# picB4currentreading.net
KiCad netlist of a schematic drawn in EAGLE
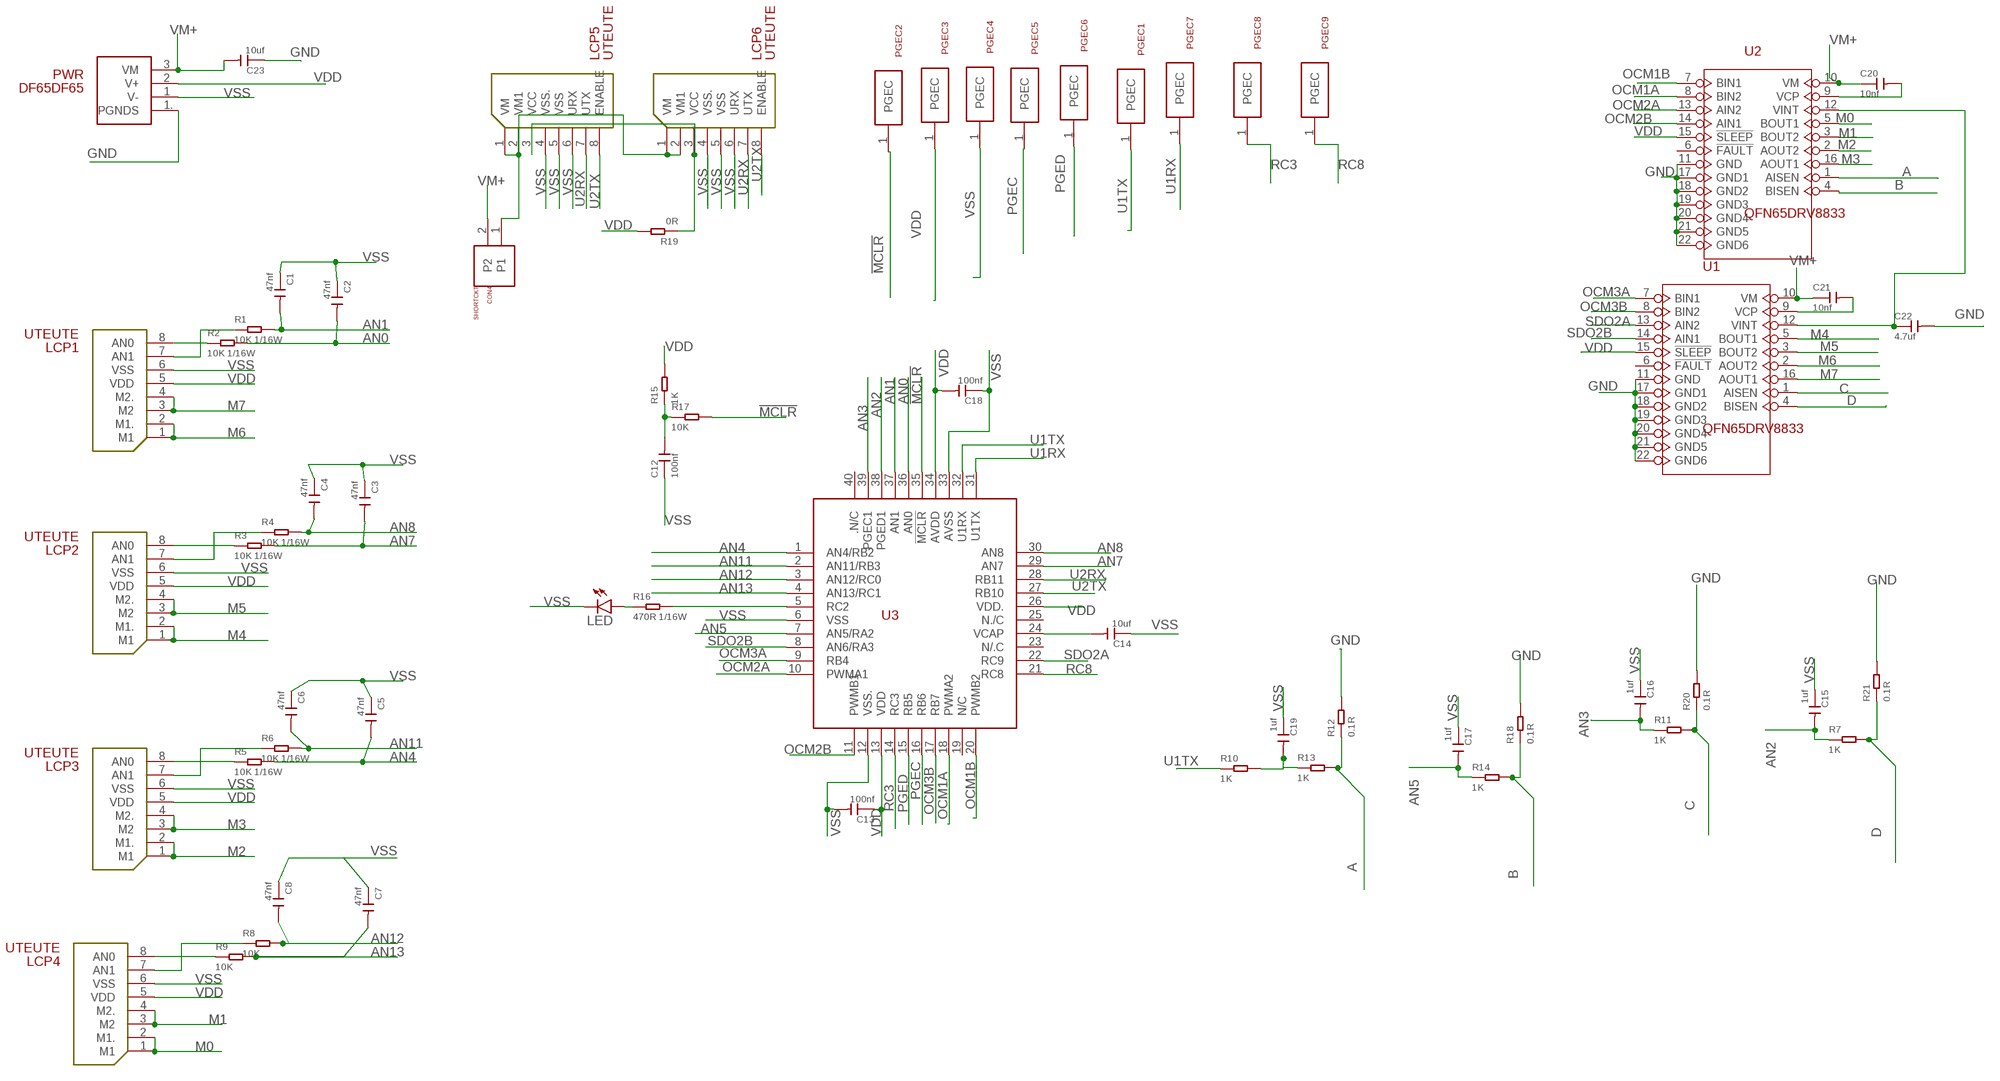
[diagram p0: schematic, sheet 1]

(export (version "E")
  (design (tool "Eeschema 10.0.6"))
  (components
    (comp (ref "C1")
      (value "47nf")
      (footprint "eagle-import:C0402")
      (fields (field (name "MPN") "CC0402KRX7R8BB473"))
      (libsource (lib "eagle-import") (part "CERAMIC-47NF-25V-10%-X7R(0402)"))
    )
    (comp (ref "C2")
      (value "47nf")
      (footprint "eagle-import:C0402")
      (fields (field (name "MPN") "CC0402KRX7R8BB473"))
      (libsource (lib "eagle-import") (part "CERAMIC-47NF-25V-10%-X7R(0402)"))
    )
    (comp (ref "C3")
      (value "47nf")
      (footprint "eagle-import:C0402")
      (fields (field (name "MPN") "CC0402KRX7R8BB473"))
      (libsource (lib "eagle-import") (part "CERAMIC-47NF-25V-10%-X7R(0402)"))
    )
    (comp (ref "C4")
      (value "47nf")
      (footprint "eagle-import:C0402")
      (fields (field (name "MPN") "CC0402KRX7R8BB473"))
      (libsource (lib "eagle-import") (part "CERAMIC-47NF-25V-10%-X7R(0402)"))
    )
    (comp (ref "C5")
      (value "47nf")
      (footprint "eagle-import:C0402")
      (fields (field (name "MPN") "CC0402KRX7R8BB473"))
      (libsource (lib "eagle-import") (part "CERAMIC-47NF-25V-10%-X7R(0402)"))
    )
    (comp (ref "C6")
      (value "47nf")
      (footprint "eagle-import:C0402")
      (fields (field (name "MPN") "CC0402KRX7R8BB473"))
      (libsource (lib "eagle-import") (part "CERAMIC-47NF-25V-10%-X7R(0402)"))
    )
    (comp (ref "C7")
      (value "47nf")
      (footprint "eagle-import:C0402")
      (fields (field (name "MPN") "CC0402KRX7R8BB473"))
      (libsource (lib "eagle-import") (part "CERAMIC-47NF-25V-10%-X7R(0402)"))
    )
    (comp (ref "C8")
      (value "47nf")
      (footprint "eagle-import:C0402")
      (fields (field (name "MPN") "CC0402KRX7R8BB473"))
      (libsource (lib "eagle-import") (part "CERAMIC-47NF-25V-10%-X7R(0402)"))
    )
    (comp (ref "C12")
      (value "100nf")
      (footprint "eagle-import:C0402")
      (fields (field (name "MPN") "CC0402KRX7R8BB104"))
      (libsource (lib "eagle-import") (part "CERAMIC-100NF-25V-10%-X7R(0402)"))
    )
    (comp (ref "C13")
      (value "100nf")
      (footprint "eagle-import:C0402")
      (fields (field (name "MPN") "CC0402KRX7R8BB104"))
      (libsource (lib "eagle-import") (part "CERAMIC-100NF-25V-10%-X7R(0402)"))
    )
    (comp (ref "C14")
      (value "10uf")
      (footprint "eagle-import:C0402")
      (fields (field (name "MPN") "CC0402MRX5R5BB106"))
      (libsource (lib "eagle-import") (part "CERAMIC-10UF-6.3V-20%-X5R(0402)"))
    )
    (comp (ref "C15")
      (value "1uf")
      (footprint "eagle-import:C0402")
      (fields (field (name "MPN") "CC0402KRX5R6BB105"))
      (libsource (lib "eagle-import") (part "CERAMIC-1UF-10V-10%-X5R(0402)"))
    )
    (comp (ref "C16")
      (value "1uf")
      (footprint "eagle-import:C0402")
      (fields (field (name "MPN") "CC0402KRX5R6BB105"))
      (libsource (lib "eagle-import") (part "CERAMIC-1UF-10V-10%-X5R(0402)"))
    )
    (comp (ref "C17")
      (value "1uf")
      (footprint "eagle-import:C0402")
      (fields (field (name "MPN") "CC0402KRX5R6BB105"))
      (libsource (lib "eagle-import") (part "CERAMIC-1UF-10V-10%-X5R(0402)"))
    )
    (comp (ref "C18")
      (value "100nf")
      (footprint "eagle-import:C0402")
      (fields (field (name "MPN") "CC0402KRX7R8BB104"))
      (libsource (lib "eagle-import") (part "CERAMIC-100NF-25V-10%-X7R(0402)"))
    )
    (comp (ref "C19")
      (value "1uf")
      (footprint "eagle-import:C0402")
      (fields (field (name "MPN") "CC0402KRX5R6BB105"))
      (libsource (lib "eagle-import") (part "CERAMIC-1UF-10V-10%-X5R(0402)"))
    )
    (comp (ref "C20")
      (value "10nf")
      (footprint "eagle-import:C0402")
      (fields (field (name "MPN") "CC0402KRX7R9BB103"))
      (libsource (lib "eagle-import") (part "CERAMIC-10NF-50V-10%-X7R(0402)"))
    )
    (comp (ref "C21")
      (value "10nf")
      (footprint "eagle-import:C0402")
      (fields (field (name "MPN") "CC0402KRX7R9BB103"))
      (libsource (lib "eagle-import") (part "CERAMIC-10NF-50V-10%-X7R(0402)"))
    )
    (comp (ref "C22")
      (value "4.7uf")
      (footprint "eagle-import:C0402")
      (fields (field (name "MPN") "CC0402MRX5R5BB475"))
      (libsource (lib "eagle-import") (part "CERAMIC-4.7UF-6.3V-20%-X5R(0402)"))
    )
    (comp (ref "C23")
      (value "10uf")
      (footprint "eagle-import:C0402")
      (fields (field (name "MPN") "CC0402MRX5R5BB106"))
      (libsource (lib "eagle-import") (part "CERAMIC-10UF-6.3V-20%-X5R(0402)"))
    )
    (comp (ref "CON4")
      (value "SHORTCKT")
      (footprint "eagle-import:SHORT")
      (libsource (lib "eagle-import") (part "SHORTCKT"))
    )
    (comp (ref "LCP1")
      (value "UTEUTE")
      (footprint "eagle-import:UTE")
      (libsource (lib "eagle-import") (part "UTEUTE"))
    )
    (comp (ref "LCP2")
      (value "UTEUTE")
      (footprint "eagle-import:UTE")
      (libsource (lib "eagle-import") (part "UTEUTE"))
    )
    (comp (ref "LCP3")
      (value "UTEUTE")
      (footprint "eagle-import:UTE")
      (libsource (lib "eagle-import") (part "UTEUTE"))
    )
    (comp (ref "LCP4")
      (value "UTEUTE")
      (footprint "eagle-import:UTE")
      (libsource (lib "eagle-import") (part "UTEUTE"))
    )
    (comp (ref "LCP5")
      (value "UTEUTE")
      (footprint "eagle-import:UTE")
      (libsource (lib "eagle-import") (part "ute5526(uart)_UTEUTE"))
    )
    (comp (ref "LCP6")
      (value "UTEUTE")
      (footprint "eagle-import:UTE")
      (libsource (lib "eagle-import") (part "ute5526(uart)_UTEUTE"))
    )
    (comp (ref "LED")
      (value "LEDCHIP-LED0603")
      (footprint "eagle-import:CHIP-LED0603")
      (libsource (lib "eagle-import") (part "LEDCHIP-LED0603"))
    )
    (comp (ref "PGEC1")
      (value "PGECPGEC")
      (footprint "eagle-import:PGEC")
      (libsource (lib "eagle-import") (part "PGECPGEC"))
    )
    (comp (ref "PGEC2")
      (value "PGECPGEC")
      (footprint "eagle-import:PGEC")
      (libsource (lib "eagle-import") (part "PGECPGEC"))
    )
    (comp (ref "PGEC3")
      (value "PGECPGEC")
      (footprint "eagle-import:PGEC")
      (libsource (lib "eagle-import") (part "PGECPGEC"))
    )
    (comp (ref "PGEC4")
      (value "PGECPGEC")
      (footprint "eagle-import:PGEC")
      (libsource (lib "eagle-import") (part "PGECPGEC"))
    )
    (comp (ref "PGEC5")
      (value "PGECPGEC")
      (footprint "eagle-import:PGEC")
      (libsource (lib "eagle-import") (part "PGECPGEC"))
    )
    (comp (ref "PGEC6")
      (value "PGECPGEC")
      (footprint "eagle-import:PGEC")
      (libsource (lib "eagle-import") (part "PGECPGEC"))
    )
    (comp (ref "PGEC7")
      (value "PGECPGEC")
      (footprint "eagle-import:PGEC")
      (libsource (lib "eagle-import") (part "PGECPGEC"))
    )
    (comp (ref "PGEC8")
      (value "PGECPGEC")
      (footprint "eagle-import:PGEC")
      (libsource (lib "eagle-import") (part "PGECPGEC"))
    )
    (comp (ref "PGEC9")
      (value "PGECPGEC")
      (footprint "eagle-import:PGEC")
      (libsource (lib "eagle-import") (part "PGECPGEC"))
    )
    (comp (ref "PWR")
      (value "DF65DF65")
      (footprint "eagle-import:DF65")
      (libsource (lib "eagle-import") (part "DF65DF65"))
    )
    (comp (ref "R1")
      (value "10K 1/16W")
      (footprint "eagle-import:R0402")
      (fields (field (name "MPN") "RC0402FR-0710KL"))
      (libsource (lib "eagle-import") (part "SMD-RES-10K-1%-1/16W(0402)"))
    )
    (comp (ref "R2")
      (value "10K 1/16W")
      (footprint "eagle-import:R0402")
      (fields (field (name "MPN") "RC0402FR-0710KL"))
      (libsource (lib "eagle-import") (part "SMD-RES-10K-1%-1/16W(0402)"))
    )
    (comp (ref "R3")
      (value "10K 1/16W")
      (footprint "eagle-import:R0402")
      (fields (field (name "MPN") "RC0402FR-0710KL"))
      (libsource (lib "eagle-import") (part "SMD-RES-10K-1%-1/16W(0402)"))
    )
    (comp (ref "R4")
      (value "10K 1/16W")
      (footprint "eagle-import:R0402")
      (fields (field (name "MPN") "RC0402FR-0710KL"))
      (libsource (lib "eagle-import") (part "SMD-RES-10K-1%-1/16W(0402)"))
    )
    (comp (ref "R5")
      (value "10K 1/16W")
      (footprint "eagle-import:R0402")
      (fields (field (name "MPN") "RC0402FR-0710KL"))
      (libsource (lib "eagle-import") (part "SMD-RES-10K-1%-1/16W(0402)"))
    )
    (comp (ref "R6")
      (value "10K 1/16W")
      (footprint "eagle-import:R0402")
      (fields (field (name "MPN") "RC0402FR-0710KL"))
      (libsource (lib "eagle-import") (part "SMD-RES-10K-1%-1/16W(0402)"))
    )
    (comp (ref "R7")
      (value "1K")
      (footprint "eagle-import:R0402")
      (fields (field (name "MPN") "RC0402JR-071KL"))
      (libsource (lib "eagle-import") (part "SMD-RES-1K-5%-1/16W(0402)"))
    )
    (comp (ref "R8")
      (value "10K")
      (footprint "eagle-import:R0402")
      (fields (field (name "MPN") "RC0402JR-0710KL"))
      (libsource (lib "eagle-import") (part "SMD-RES-10K-5%-1/(0402)"))
    )
    (comp (ref "R9")
      (value "10K")
      (footprint "eagle-import:R0402")
      (fields (field (name "MPN") "RC0402JR-0710KL"))
      (libsource (lib "eagle-import") (part "SMD-RES-10K-5%-1/(0402)"))
    )
    (comp (ref "R10")
      (value "1K")
      (footprint "eagle-import:R0402")
      (fields (field (name "MPN") "RC0402JR-071KL"))
      (libsource (lib "eagle-import") (part "SMD-RES-1K-5%-1/16W(0402)"))
    )
    (comp (ref "R11")
      (value "1K")
      (footprint "eagle-import:R0402")
      (fields (field (name "MPN") "RC0402JR-071KL"))
      (libsource (lib "eagle-import") (part "SMD-RES-1K-5%-1/16W(0402)"))
    )
    (comp (ref "R12")
      (value "0.1R")
      (footprint "eagle-import:R0805")
      (fields (field (name "MPN") "RL0805JR-070R1L"))
      (libsource (lib "eagle-import") (part "SMD-RES-0.1R-5%-1/8W(0805)"))
    )
    (comp (ref "R13")
      (value "1K")
      (footprint "eagle-import:R0402")
      (fields (field (name "MPN") "RC0402JR-071KL"))
      (libsource (lib "eagle-import") (part "SMD-RES-1K-5%-1/16W(0402)"))
    )
    (comp (ref "R14")
      (value "1K")
      (footprint "eagle-import:R0402")
      (fields (field (name "MPN") "RC0402JR-071KL"))
      (libsource (lib "eagle-import") (part "SMD-RES-1K-5%-1/16W(0402)"))
    )
    (comp (ref "R15")
      (value "1K")
      (footprint "eagle-import:R0402")
      (fields (field (name "MPN") "RC0402JR-071KL"))
      (libsource (lib "eagle-import") (part "SMD-RES-1K-5%-1/16W(0402)"))
    )
    (comp (ref "R16")
      (value "470R 1/16W")
      (footprint "eagle-import:R0402")
      (fields (field (name "MPN") "RC0402JR-07470RL"))
      (libsource (lib "eagle-import") (part "SMD-RES-470R-5%-1/16W(0402)"))
    )
    (comp (ref "R17")
      (value "10K")
      (footprint "eagle-import:R0402")
      (fields (field (name "MPN") "RC0402JR-0710KL"))
      (libsource (lib "eagle-import") (part "SMD-RES-10K-5%-1/(0402)"))
    )
    (comp (ref "R18")
      (value "0.1R")
      (footprint "eagle-import:R0805")
      (fields (field (name "MPN") "RL0805JR-070R1L"))
      (libsource (lib "eagle-import") (part "SMD-RES-0.1R-5%-1/8W(0805)"))
    )
    (comp (ref "R19")
      (value "0R")
      (footprint "eagle-import:R0402")
      (fields (field (name "MPN") "RC0402JR-070RL"))
      (libsource (lib "eagle-import") (part "SMD-RES-0R-5%-1/16W(0402)"))
    )
    (comp (ref "R20")
      (value "0.1R")
      (footprint "eagle-import:R0805")
      (fields (field (name "MPN") "RL0805JR-070R1L"))
      (libsource (lib "eagle-import") (part "SMD-RES-0.1R-5%-1/8W(0805)"))
    )
    (comp (ref "R21")
      (value "0.1R")
      (footprint "eagle-import:R0805")
      (fields (field (name "MPN") "RL0805JR-070R1L"))
      (libsource (lib "eagle-import") (part "SMD-RES-0.1R-5%-1/8W(0805)"))
    )
    (comp (ref "U1")
      (value "QFN65DRV8833")
      (footprint "eagle-import:QFN65P400X400X80-17N")
      (libsource (lib "eagle-import") (part "QFN65DRV8833"))
    )
    (comp (ref "U2")
      (value "QFN65DRV8833")
      (footprint "eagle-import:QFN65P400X400X80-17N")
      (libsource (lib "eagle-import") (part "QFN65DRV8833"))
    )
    (comp (ref "U3")
      (value "PIC32MM0064GPL036PIC32MM0064GPL36")
      (footprint "eagle-import:UQFN40MV5X5MM")
      (libsource (lib "eagle-import") (part "PIC32MM0064GPL036PIC32MM0064GPL36"))
    )
  )
  (nets
    (net (code "1") (name "/A") (class "Default")
      (node (ref "R12") (pin "1") (pinfunction "1_1") (pintype "passive"))
      (node (ref "R13") (pin "2") (pinfunction "2_2") (pintype "passive"))
      (node (ref "U2") (pin "1") (pinfunction "AISEN_1") (pintype "bidirectional"))
    )
    (net (code "2") (name "/AN0") (class "Default")
      (node (ref "C2") (pin "2") (pinfunction "2_2") (pintype "passive"))
      (node (ref "R2") (pin "2") (pinfunction "2_2") (pintype "passive"))
      (node (ref "U3") (pin "36") (pinfunction "AN0_36") (pintype "bidirectional"))
    )
    (net (code "3") (name "/AN1") (class "Default")
      (node (ref "C1") (pin "2") (pinfunction "2_2") (pintype "passive"))
      (node (ref "R1") (pin "2") (pinfunction "2_2") (pintype "passive"))
      (node (ref "U3") (pin "37") (pinfunction "AN1_37") (pintype "bidirectional"))
    )
    (net (code "4") (name "/AN2") (class "Default")
      (node (ref "C15") (pin "2") (pinfunction "2_2") (pintype "passive"))
      (node (ref "R7") (pin "1") (pinfunction "1_1") (pintype "passive"))
      (node (ref "U3") (pin "38") (pinfunction "PGED1_38") (pintype "bidirectional"))
    )
    (net (code "5") (name "/AN3") (class "Default")
      (node (ref "C16") (pin "2") (pinfunction "2_2") (pintype "passive"))
      (node (ref "R11") (pin "1") (pinfunction "1_1") (pintype "passive"))
      (node (ref "U3") (pin "39") (pinfunction "PGEC1_39") (pintype "bidirectional"))
    )
    (net (code "6") (name "/AN4") (class "Default")
      (node (ref "C5") (pin "2") (pinfunction "2_2") (pintype "passive"))
      (node (ref "R5") (pin "2") (pinfunction "2_2") (pintype "passive"))
      (node (ref "U3") (pin "1") (pinfunction "AN4/RB2_1") (pintype "bidirectional"))
    )
    (net (code "7") (name "/AN5") (class "Default")
      (node (ref "C17") (pin "2") (pinfunction "2_2") (pintype "passive"))
      (node (ref "R14") (pin "1") (pinfunction "1_1") (pintype "passive"))
      (node (ref "U3") (pin "7") (pinfunction "AN5/RA2_7") (pintype "bidirectional"))
    )
    (net (code "8") (name "/AN7") (class "Default")
      (node (ref "C3") (pin "2") (pinfunction "2_2") (pintype "passive"))
      (node (ref "R3") (pin "2") (pinfunction "2_2") (pintype "passive"))
      (node (ref "U3") (pin "29") (pinfunction "AN7_29") (pintype "bidirectional"))
    )
    (net (code "9") (name "/AN8") (class "Default")
      (node (ref "C4") (pin "2") (pinfunction "2_2") (pintype "passive"))
      (node (ref "R4") (pin "2") (pinfunction "2_2") (pintype "passive"))
      (node (ref "U3") (pin "30") (pinfunction "AN8_30") (pintype "bidirectional"))
    )
    (net (code "10") (name "/AN11") (class "Default")
      (node (ref "C6") (pin "2") (pinfunction "2_2") (pintype "passive"))
      (node (ref "R6") (pin "2") (pinfunction "2_2") (pintype "passive"))
      (node (ref "U3") (pin "2") (pinfunction "AN11/RB3_2") (pintype "bidirectional"))
    )
    (net (code "11") (name "/AN12") (class "Default")
      (node (ref "C8") (pin "2") (pinfunction "2_2") (pintype "passive"))
      (node (ref "R8") (pin "2") (pinfunction "2_2") (pintype "passive"))
      (node (ref "U3") (pin "3") (pinfunction "AN12/RC0_3") (pintype "bidirectional"))
    )
    (net (code "12") (name "/AN13") (class "Default")
      (node (ref "C7") (pin "2") (pinfunction "2_2") (pintype "passive"))
      (node (ref "R9") (pin "2") (pinfunction "2_2") (pintype "passive"))
      (node (ref "U3") (pin "4") (pinfunction "AN13/RC1_4") (pintype "bidirectional"))
    )
    (net (code "13") (name "/B") (class "Default")
      (node (ref "R14") (pin "2") (pinfunction "2_2") (pintype "passive"))
      (node (ref "R18") (pin "1") (pinfunction "1_1") (pintype "passive"))
      (node (ref "U2") (pin "4") (pinfunction "BISEN_4") (pintype "bidirectional"))
    )
    (net (code "14") (name "/C") (class "Default")
      (node (ref "R11") (pin "2") (pinfunction "2_2") (pintype "passive"))
      (node (ref "R20") (pin "1") (pinfunction "1_1") (pintype "passive"))
      (node (ref "U1") (pin "1") (pinfunction "AISEN_1") (pintype "bidirectional"))
    )
    (net (code "15") (name "/D") (class "Default")
      (node (ref "R21") (pin "1") (pinfunction "1_1") (pintype "passive"))
      (node (ref "R7") (pin "2") (pinfunction "2_2") (pintype "passive"))
      (node (ref "U1") (pin "4") (pinfunction "BISEN_4") (pintype "bidirectional"))
    )
    (net (code "16") (name "/GND") (class "Default")
      (node (ref "C22") (pin "2") (pinfunction "2_2") (pintype "passive"))
      (node (ref "C23") (pin "1") (pinfunction "1_1") (pintype "passive"))
      (node (ref "PWR") (pin "1.") (pinfunction "PGNDS_1.") (pintype "bidirectional"))
      (node (ref "R12") (pin "2") (pinfunction "2_2") (pintype "passive"))
      (node (ref "R18") (pin "2") (pinfunction "2_2") (pintype "passive"))
      (node (ref "R20") (pin "2") (pinfunction "2_2") (pintype "passive"))
      (node (ref "R21") (pin "2") (pinfunction "2_2") (pintype "passive"))
      (node (ref "U1") (pin "11") (pinfunction "GND_11") (pintype "bidirectional"))
      (node (ref "U1") (pin "17") (pinfunction "GND1_17") (pintype "bidirectional"))
      (node (ref "U1") (pin "18") (pinfunction "GND2_18") (pintype "bidirectional"))
      (node (ref "U1") (pin "19") (pinfunction "GND3_19") (pintype "bidirectional"))
      (node (ref "U1") (pin "20") (pinfunction "GND4_20") (pintype "bidirectional"))
      (node (ref "U1") (pin "21") (pinfunction "GND5_21") (pintype "bidirectional"))
      (node (ref "U1") (pin "22") (pinfunction "GND6_22") (pintype "bidirectional"))
      (node (ref "U2") (pin "11") (pinfunction "GND_11") (pintype "bidirectional"))
      (node (ref "U2") (pin "17") (pinfunction "GND1_17") (pintype "bidirectional"))
      (node (ref "U2") (pin "18") (pinfunction "GND2_18") (pintype "bidirectional"))
      (node (ref "U2") (pin "19") (pinfunction "GND3_19") (pintype "bidirectional"))
      (node (ref "U2") (pin "20") (pinfunction "GND4_20") (pintype "bidirectional"))
      (node (ref "U2") (pin "21") (pinfunction "GND5_21") (pintype "bidirectional"))
      (node (ref "U2") (pin "22") (pinfunction "GND6_22") (pintype "bidirectional"))
    )
    (net (code "17") (name "/M0") (class "Default")
      (node (ref "LCP4") (pin "1") (pinfunction "M1_1") (pintype "bidirectional"))
      (node (ref "LCP4") (pin "2") (pinfunction "M1._2") (pintype "bidirectional"))
      (node (ref "U2") (pin "5") (pinfunction "BOUT1_5") (pintype "bidirectional"))
    )
    (net (code "18") (name "/M1") (class "Default")
      (node (ref "LCP4") (pin "3") (pinfunction "M2_3") (pintype "bidirectional"))
      (node (ref "LCP4") (pin "4") (pinfunction "M2._4") (pintype "bidirectional"))
      (node (ref "U2") (pin "3") (pinfunction "BOUT2_3") (pintype "bidirectional"))
    )
    (net (code "19") (name "/M2") (class "Default")
      (node (ref "LCP3") (pin "1") (pinfunction "M1_1") (pintype "bidirectional"))
      (node (ref "LCP3") (pin "2") (pinfunction "M1._2") (pintype "bidirectional"))
      (node (ref "U2") (pin "2") (pinfunction "AOUT2_2") (pintype "bidirectional"))
    )
    (net (code "20") (name "/M3") (class "Default")
      (node (ref "LCP3") (pin "3") (pinfunction "M2_3") (pintype "bidirectional"))
      (node (ref "LCP3") (pin "4") (pinfunction "M2._4") (pintype "bidirectional"))
      (node (ref "U2") (pin "16") (pinfunction "AOUT1_16") (pintype "bidirectional"))
    )
    (net (code "21") (name "/M4") (class "Default")
      (node (ref "LCP2") (pin "1") (pinfunction "M1_1") (pintype "bidirectional"))
      (node (ref "LCP2") (pin "2") (pinfunction "M1._2") (pintype "bidirectional"))
      (node (ref "U1") (pin "5") (pinfunction "BOUT1_5") (pintype "bidirectional"))
    )
    (net (code "22") (name "/M5") (class "Default")
      (node (ref "LCP2") (pin "3") (pinfunction "M2_3") (pintype "bidirectional"))
      (node (ref "LCP2") (pin "4") (pinfunction "M2._4") (pintype "bidirectional"))
      (node (ref "U1") (pin "3") (pinfunction "BOUT2_3") (pintype "bidirectional"))
    )
    (net (code "23") (name "/M6") (class "Default")
      (node (ref "LCP1") (pin "1") (pinfunction "M1_1") (pintype "bidirectional"))
      (node (ref "LCP1") (pin "2") (pinfunction "M1._2") (pintype "bidirectional"))
      (node (ref "U1") (pin "2") (pinfunction "AOUT2_2") (pintype "bidirectional"))
    )
    (net (code "24") (name "/M7") (class "Default")
      (node (ref "LCP1") (pin "3") (pinfunction "M2_3") (pintype "bidirectional"))
      (node (ref "LCP1") (pin "4") (pinfunction "M2._4") (pintype "bidirectional"))
      (node (ref "U1") (pin "16") (pinfunction "AOUT1_16") (pintype "bidirectional"))
    )
    (net (code "25") (name "/OCM1A") (class "Default")
      (node (ref "U2") (pin "8") (pinfunction "BIN2_8") (pintype "bidirectional"))
      (node (ref "U3") (pin "18") (pinfunction "PWMA2_18") (pintype "bidirectional"))
    )
    (net (code "26") (name "/OCM1B") (class "Default")
      (node (ref "U2") (pin "7") (pinfunction "BIN1_7") (pintype "bidirectional"))
      (node (ref "U3") (pin "20") (pinfunction "PWMB2_20") (pintype "bidirectional"))
    )
    (net (code "27") (name "/OCM2A") (class "Default")
      (node (ref "U2") (pin "13") (pinfunction "AIN2_13") (pintype "bidirectional"))
      (node (ref "U3") (pin "10") (pinfunction "PWMA1_10") (pintype "bidirectional"))
    )
    (net (code "28") (name "/OCM2B") (class "Default")
      (node (ref "U2") (pin "14") (pinfunction "AIN1_14") (pintype "bidirectional"))
      (node (ref "U3") (pin "11") (pinfunction "PWMB1_11") (pintype "bidirectional"))
    )
    (net (code "29") (name "/OCM3A") (class "Default")
      (node (ref "U1") (pin "7") (pinfunction "BIN1_7") (pintype "bidirectional"))
      (node (ref "U3") (pin "9") (pinfunction "RB4_9") (pintype "bidirectional"))
    )
    (net (code "30") (name "/OCM3B") (class "Default")
      (node (ref "U1") (pin "8") (pinfunction "BIN2_8") (pintype "bidirectional"))
      (node (ref "U3") (pin "17") (pinfunction "RB7_17") (pintype "bidirectional"))
    )
    (net (code "31") (name "/PGEC") (class "Default")
      (node (ref "PGEC5") (pin "1") (pinfunction "PGEC_1") (pintype "bidirectional"))
      (node (ref "U3") (pin "16") (pinfunction "RB6_16") (pintype "bidirectional"))
    )
    (net (code "32") (name "/PGED") (class "Default")
      (node (ref "PGEC6") (pin "1") (pinfunction "PGEC_1") (pintype "bidirectional"))
      (node (ref "U3") (pin "15") (pinfunction "RB5_15") (pintype "bidirectional"))
    )
    (net (code "33") (name "/RC3") (class "Default")
      (node (ref "PGEC8") (pin "1") (pinfunction "PGEC_1") (pintype "bidirectional"))
      (node (ref "U3") (pin "14") (pinfunction "RC3_14") (pintype "bidirectional"))
    )
    (net (code "34") (name "/RC8") (class "Default")
      (node (ref "PGEC9") (pin "1") (pinfunction "PGEC_1") (pintype "bidirectional"))
      (node (ref "U3") (pin "21") (pinfunction "RC8_21") (pintype "bidirectional"))
    )
    (net (code "35") (name "/SDO2A") (class "Default")
      (node (ref "U1") (pin "13") (pinfunction "AIN2_13") (pintype "bidirectional"))
      (node (ref "U3") (pin "22") (pinfunction "RC9_22") (pintype "bidirectional"))
    )
    (net (code "36") (name "/SDO2B") (class "Default")
      (node (ref "U1") (pin "14") (pinfunction "AIN1_14") (pintype "bidirectional"))
      (node (ref "U3") (pin "8") (pinfunction "AN6/RA3_8") (pintype "bidirectional"))
    )
    (net (code "37") (name "/U1RX") (class "Default")
      (node (ref "PGEC7") (pin "1") (pinfunction "PGEC_1") (pintype "bidirectional"))
      (node (ref "U3") (pin "31") (pinfunction "U1TX_31") (pintype "bidirectional"))
    )
    (net (code "38") (name "/U1TX") (class "Default")
      (node (ref "PGEC1") (pin "1") (pinfunction "PGEC_1") (pintype "bidirectional"))
      (node (ref "R10") (pin "1") (pinfunction "1_1") (pintype "passive"))
      (node (ref "U3") (pin "32") (pinfunction "U1RX_32") (pintype "bidirectional"))
    )
    (net (code "39") (name "/U2RX") (class "Default")
      (node (ref "LCP5") (pin "7") (pinfunction "UTX_7") (pintype "bidirectional"))
      (node (ref "LCP6") (pin "7") (pinfunction "UTX_7") (pintype "bidirectional"))
      (node (ref "U3") (pin "28") (pinfunction "RB11_28") (pintype "bidirectional"))
    )
    (net (code "40") (name "/U2TX") (class "Default")
      (node (ref "LCP5") (pin "8") (pinfunction "ENABLE_8") (pintype "bidirectional"))
      (node (ref "LCP6") (pin "8") (pinfunction "ENABLE_8") (pintype "bidirectional"))
      (node (ref "U3") (pin "27") (pinfunction "RB10_27") (pintype "bidirectional"))
    )
    (net (code "41") (name "/VDD") (class "Default")
      (node (ref "C13") (pin "1") (pinfunction "1_1") (pintype "passive"))
      (node (ref "C18") (pin "2") (pinfunction "2_2") (pintype "passive"))
      (node (ref "LCP1") (pin "5") (pinfunction "VDD_5") (pintype "bidirectional"))
      (node (ref "LCP2") (pin "5") (pinfunction "VDD_5") (pintype "bidirectional"))
      (node (ref "LCP3") (pin "5") (pinfunction "VDD_5") (pintype "bidirectional"))
      (node (ref "LCP4") (pin "5") (pinfunction "VDD_5") (pintype "bidirectional"))
      (node (ref "PGEC3") (pin "1") (pinfunction "PGEC_1") (pintype "bidirectional"))
      (node (ref "PWR") (pin "2") (pinfunction "V+_2") (pintype "bidirectional"))
      (node (ref "R15") (pin "2") (pinfunction "2_2") (pintype "passive"))
      (node (ref "R19") (pin "2") (pinfunction "2_2") (pintype "passive"))
      (node (ref "U1") (pin "15") (pinfunction "~{SLEEP}_15") (pintype "bidirectional"))
      (node (ref "U2") (pin "15") (pinfunction "~{SLEEP}_15") (pintype "bidirectional"))
      (node (ref "U3") (pin "13") (pinfunction "VDD_13") (pintype "bidirectional"))
      (node (ref "U3") (pin "26") (pinfunction "VDD._26") (pintype "bidirectional"))
      (node (ref "U3") (pin "34") (pinfunction "AVDD_34") (pintype "bidirectional"))
    )
    (net (code "42") (name "/VM+") (class "Default")
      (node (ref "C20") (pin "1") (pinfunction "1_1") (pintype "passive"))
      (node (ref "C21") (pin "1") (pinfunction "1_1") (pintype "passive"))
      (node (ref "C23") (pin "2") (pinfunction "2_2") (pintype "passive"))
      (node (ref "CON4") (pin "2") (pinfunction "P2_2") (pintype "bidirectional"))
      (node (ref "PWR") (pin "3") (pinfunction "VM_3") (pintype "bidirectional"))
      (node (ref "U1") (pin "10") (pinfunction "VM_10") (pintype "bidirectional"))
      (node (ref "U2") (pin "10") (pinfunction "VM_10") (pintype "bidirectional"))
    )
    (net (code "43") (name "/VSS") (class "Default")
      (node (ref "C1") (pin "1") (pinfunction "1_1") (pintype "passive"))
      (node (ref "C12") (pin "1") (pinfunction "1_1") (pintype "passive"))
      (node (ref "C13") (pin "2") (pinfunction "2_2") (pintype "passive"))
      (node (ref "C14") (pin "1") (pinfunction "1_1") (pintype "passive"))
      (node (ref "C15") (pin "1") (pinfunction "1_1") (pintype "passive"))
      (node (ref "C16") (pin "1") (pinfunction "1_1") (pintype "passive"))
      (node (ref "C17") (pin "1") (pinfunction "1_1") (pintype "passive"))
      (node (ref "C18") (pin "1") (pinfunction "1_1") (pintype "passive"))
      (node (ref "C19") (pin "1") (pinfunction "1_1") (pintype "passive"))
      (node (ref "C2") (pin "1") (pinfunction "1_1") (pintype "passive"))
      (node (ref "C3") (pin "1") (pinfunction "1_1") (pintype "passive"))
      (node (ref "C4") (pin "1") (pinfunction "1_1") (pintype "passive"))
      (node (ref "C5") (pin "1") (pinfunction "1_1") (pintype "passive"))
      (node (ref "C6") (pin "1") (pinfunction "1_1") (pintype "passive"))
      (node (ref "C7") (pin "1") (pinfunction "1_1") (pintype "passive"))
      (node (ref "C8") (pin "1") (pinfunction "1_1") (pintype "passive"))
      (node (ref "LCP1") (pin "6") (pinfunction "VSS_6") (pintype "bidirectional"))
      (node (ref "LCP2") (pin "6") (pinfunction "VSS_6") (pintype "bidirectional"))
      (node (ref "LCP3") (pin "6") (pinfunction "VSS_6") (pintype "bidirectional"))
      (node (ref "LCP4") (pin "6") (pinfunction "VSS_6") (pintype "bidirectional"))
      (node (ref "LCP5") (pin "4") (pinfunction "VSS._4") (pintype "bidirectional"))
      (node (ref "LCP5") (pin "5") (pinfunction "VSS_5") (pintype "bidirectional"))
      (node (ref "LCP5") (pin "6") (pinfunction "URX_6") (pintype "bidirectional"))
      (node (ref "LCP6") (pin "4") (pinfunction "VSS._4") (pintype "bidirectional"))
      (node (ref "LCP6") (pin "5") (pinfunction "VSS_5") (pintype "bidirectional"))
      (node (ref "LCP6") (pin "6") (pinfunction "URX_6") (pintype "bidirectional"))
      (node (ref "LED") (pin "C") (pinfunction "C_C") (pintype "passive"))
      (node (ref "PGEC4") (pin "1") (pinfunction "PGEC_1") (pintype "bidirectional"))
      (node (ref "PWR") (pin "1") (pinfunction "V-_1") (pintype "bidirectional"))
      (node (ref "U3") (pin "12") (pinfunction "VSS._12") (pintype "bidirectional"))
      (node (ref "U3") (pin "33") (pinfunction "AVSS_33") (pintype "bidirectional"))
      (node (ref "U3") (pin "6") (pinfunction "VSS_6") (pintype "bidirectional"))
    )
    (net (code "44") (name "/~{MCLR}") (class "Default")
      (node (ref "PGEC2") (pin "1") (pinfunction "PGEC_1") (pintype "bidirectional"))
      (node (ref "R17") (pin "2") (pinfunction "2_2") (pintype "passive"))
      (node (ref "U3") (pin "35") (pinfunction "~{MCLR}_35") (pintype "bidirectional"))
    )
    (net (code "45") (name "Net-(C12-Pad2)") (class "Default")
      (node (ref "C12") (pin "2") (pinfunction "2_2") (pintype "passive"))
      (node (ref "R15") (pin "1") (pinfunction "1_1") (pintype "passive"))
      (node (ref "R17") (pin "1") (pinfunction "1_1") (pintype "passive"))
    )
    (net (code "46") (name "Net-(C19-Pad2)") (class "Default")
      (node (ref "C19") (pin "2") (pinfunction "2_2") (pintype "passive"))
      (node (ref "R10") (pin "2") (pinfunction "2_2") (pintype "passive"))
      (node (ref "R13") (pin "1") (pinfunction "1_1") (pintype "passive"))
    )
    (net (code "47") (name "Net-(CON4-P1)") (class "Default")
      (node (ref "CON4") (pin "1") (pinfunction "P1_1") (pintype "bidirectional"))
      (node (ref "LCP5") (pin "1") (pinfunction "VM_1") (pintype "bidirectional"))
      (node (ref "LCP5") (pin "2") (pinfunction "VM1_2") (pintype "bidirectional"))
      (node (ref "LCP6") (pin "1") (pinfunction "VM_1") (pintype "bidirectional"))
      (node (ref "LCP6") (pin "2") (pinfunction "VM1_2") (pintype "bidirectional"))
    )
    (net (code "48") (name "Net-(LCP1-AN0)") (class "Default")
      (node (ref "LCP1") (pin "8") (pinfunction "AN0_8") (pintype "bidirectional"))
      (node (ref "R2") (pin "1") (pinfunction "1_1") (pintype "passive"))
    )
    (net (code "49") (name "Net-(LCP1-AN1)") (class "Default")
      (node (ref "LCP1") (pin "7") (pinfunction "AN1_7") (pintype "bidirectional"))
      (node (ref "R1") (pin "1") (pinfunction "1_1") (pintype "passive"))
    )
    (net (code "50") (name "Net-(LCP2-AN0)") (class "Default")
      (node (ref "LCP2") (pin "8") (pinfunction "AN0_8") (pintype "bidirectional"))
      (node (ref "R3") (pin "1") (pinfunction "1_1") (pintype "passive"))
    )
    (net (code "51") (name "Net-(LCP2-AN1)") (class "Default")
      (node (ref "LCP2") (pin "7") (pinfunction "AN1_7") (pintype "bidirectional"))
      (node (ref "R4") (pin "1") (pinfunction "1_1") (pintype "passive"))
    )
    (net (code "52") (name "Net-(LCP3-AN0)") (class "Default")
      (node (ref "LCP3") (pin "8") (pinfunction "AN0_8") (pintype "bidirectional"))
      (node (ref "R5") (pin "1") (pinfunction "1_1") (pintype "passive"))
    )
    (net (code "53") (name "Net-(LCP3-AN1)") (class "Default")
      (node (ref "LCP3") (pin "7") (pinfunction "AN1_7") (pintype "bidirectional"))
      (node (ref "R6") (pin "1") (pinfunction "1_1") (pintype "passive"))
    )
    (net (code "54") (name "Net-(LCP4-AN0)") (class "Default")
      (node (ref "LCP4") (pin "8") (pinfunction "AN0_8") (pintype "bidirectional"))
      (node (ref "R9") (pin "1") (pinfunction "1_1") (pintype "passive"))
    )
    (net (code "55") (name "Net-(LCP4-AN1)") (class "Default")
      (node (ref "LCP4") (pin "7") (pinfunction "AN1_7") (pintype "bidirectional"))
      (node (ref "R8") (pin "1") (pinfunction "1_1") (pintype "passive"))
    )
    (net (code "56") (name "Net-(LCP5-VCC)") (class "Default")
      (node (ref "LCP5") (pin "3") (pinfunction "VCC_3") (pintype "bidirectional"))
      (node (ref "LCP6") (pin "3") (pinfunction "VCC_3") (pintype "bidirectional"))
      (node (ref "R19") (pin "1") (pinfunction "1_1") (pintype "passive"))
    )
    (net (code "57") (name "Net-(LED-PadA)") (class "Default")
      (node (ref "LED") (pin "A") (pinfunction "A_A") (pintype "passive"))
      (node (ref "R16") (pin "1") (pinfunction "1_1") (pintype "passive"))
    )
    (net (code "58") (name "Net-(U1-VCP)") (class "Default")
      (node (ref "C21") (pin "2") (pinfunction "2_2") (pintype "passive"))
      (node (ref "U1") (pin "9") (pinfunction "VCP_9") (pintype "bidirectional"))
    )
    (net (code "59") (name "Net-(U1-VINT)") (class "Default")
      (node (ref "C22") (pin "1") (pinfunction "1_1") (pintype "passive"))
      (node (ref "U1") (pin "12") (pinfunction "VINT_12") (pintype "bidirectional"))
      (node (ref "U2") (pin "12") (pinfunction "VINT_12") (pintype "bidirectional"))
    )
    (net (code "60") (name "Net-(U2-VCP)") (class "Default")
      (node (ref "C20") (pin "2") (pinfunction "2_2") (pintype "passive"))
      (node (ref "U2") (pin "9") (pinfunction "VCP_9") (pintype "bidirectional"))
    )
    (net (code "61") (name "Net-(U3-RC2)") (class "Default")
      (node (ref "R16") (pin "2") (pinfunction "2_2") (pintype "passive"))
      (node (ref "U3") (pin "5") (pinfunction "RC2_5") (pintype "bidirectional"))
    )
    (net (code "62") (name "Net-(U3-VCAP)") (class "Default")
      (node (ref "C14") (pin "2") (pinfunction "2_2") (pintype "passive"))
      (node (ref "U3") (pin "24") (pinfunction "VCAP_24") (pintype "bidirectional"))
    )
    (net (code "63") (name "unconnected-(U1-~{FAULT}-Pad6)") (class "Default")
      (node (ref "U1") (pin "6") (pinfunction "~{FAULT}_6") (pintype "bidirectional"))
    )
    (net (code "64") (name "unconnected-(U2-~{FAULT}-Pad6)") (class "Default")
      (node (ref "U2") (pin "6") (pinfunction "~{FAULT}_6") (pintype "bidirectional"))
    )
    (net (code "65") (name "unconnected-(U3-.N{slash}C-Pad40)") (class "Default")
      (node (ref "U3") (pin "40") (pinfunction ".N/C_40") (pintype "bidirectional"))
    )
    (net (code "66") (name "unconnected-(U3-N.{slash}C-Pad25)") (class "Default")
      (node (ref "U3") (pin "25") (pinfunction "N./C_25") (pintype "bidirectional"))
    )
    (net (code "67") (name "unconnected-(U3-N{slash}.C-Pad23)") (class "Default")
      (node (ref "U3") (pin "23") (pinfunction "N/.C_23") (pintype "bidirectional"))
    )
    (net (code "68") (name "unconnected-(U3-N{slash}C-Pad19)") (class "Default")
      (node (ref "U3") (pin "19") (pinfunction "N/C_19") (pintype "bidirectional"))
    )
  )
)
